# LoRa_Node_Module_V1_0.net
KiCad netlist of a schematic drawn in EAGLE
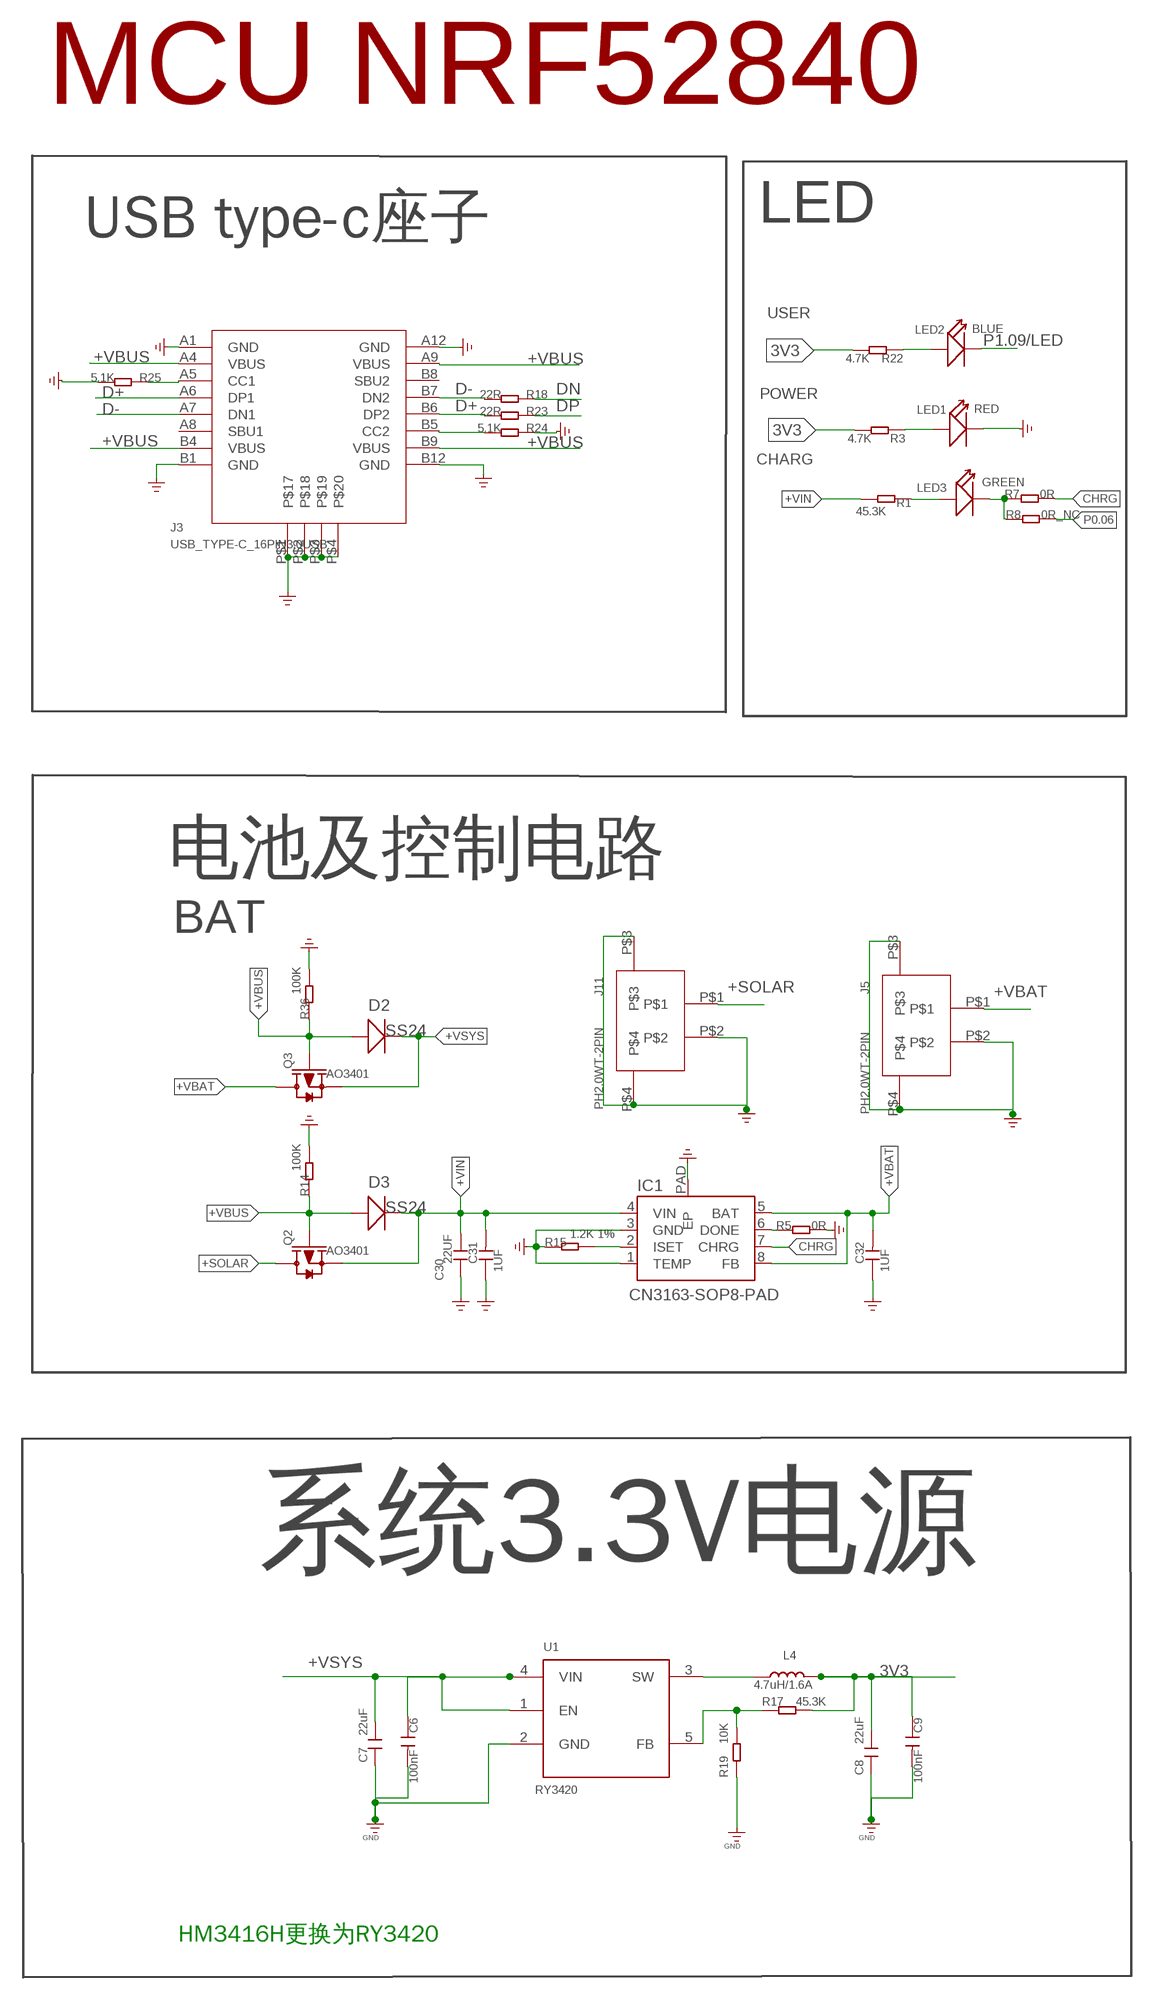
[diagram p0: schematic, sheet 1, part 1 of 2]
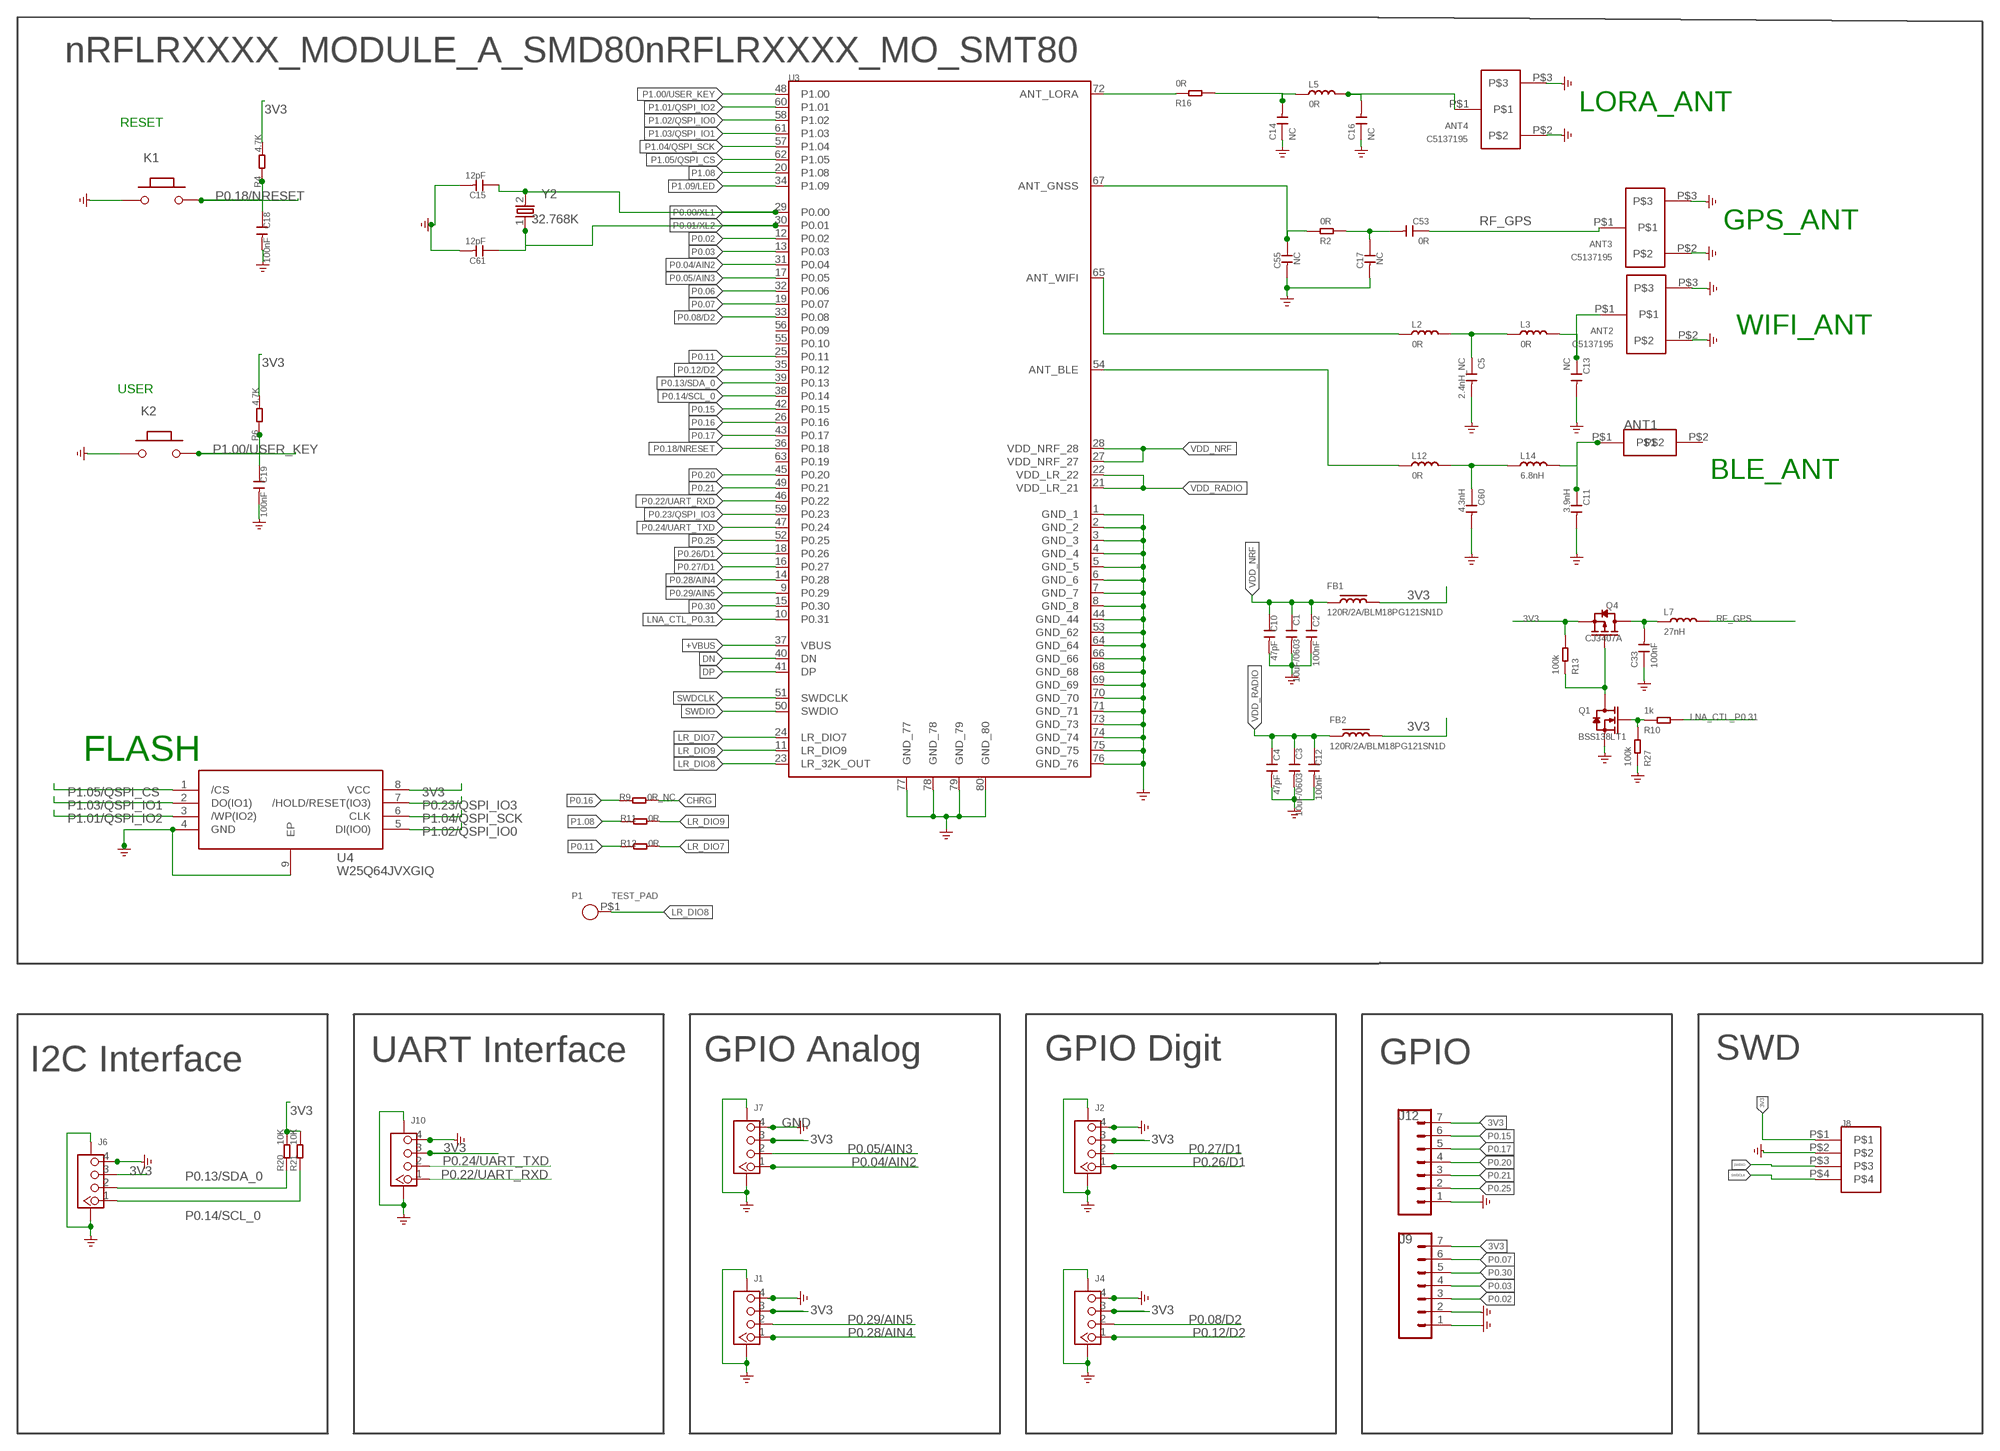
[diagram p1: schematic, sheet 1, part 2 of 2]

(export (version "E")
  (design (tool "Eeschema 10.0.6"))
  (components
    (comp (ref "ANT1")
      (value "ANT2.4G_BLE")
      (footprint "eagle-import:2.4G_BLE")
      (libsource (lib "eagle-import") (part "ANT2.4G_BLE"))
    )
    (comp (ref "ANT2")
      (value "C5137195")
      (footprint "eagle-import:MYSELF_IPEX1")
      (libsource (lib "eagle-import") (part "MYSELF_IPEX"))
    )
    (comp (ref "ANT3")
      (value "C5137195")
      (footprint "eagle-import:MYSELF_IPEX1")
      (libsource (lib "eagle-import") (part "MYSELF_IPEX"))
    )
    (comp (ref "ANT4")
      (value "C5137195")
      (footprint "eagle-import:MYSELF_IPEX1")
      (libsource (lib "eagle-import") (part "MYSELF_IPEX"))
    )
    (comp (ref "C1")
      (value "10uF/0603")
      (footprint "eagle-import:C0603")
      (libsource (lib "eagle-import") (part "C0603"))
    )
    (comp (ref "C2")
      (value "100nF")
      (footprint "eagle-import:C0402")
      (libsource (lib "eagle-import") (part "CAPC0402-1"))
    )
    (comp (ref "C3")
      (value "10uF/0603")
      (footprint "eagle-import:C0603")
      (libsource (lib "eagle-import") (part "C0603"))
    )
    (comp (ref "C4")
      (value "47pF")
      (footprint "eagle-import:C0402")
      (libsource (lib "eagle-import") (part "CAPC0402-1"))
    )
    (comp (ref "C5")
      (value "2.4nH_NC")
      (footprint "eagle-import:DISCRETE-NEW_C0402")
      (libsource (lib "eagle-import") (part "DISCRETE-NEW_CAP-0402"))
    )
    (comp (ref "C6")
      (value "100nF")
      (footprint "eagle-import:C0402")
      (libsource (lib "eagle-import") (part "CAPC0402-1"))
    )
    (comp (ref "C7")
      (value "22uF")
      (footprint "eagle-import:0603")
      (libsource (lib "eagle-import") (part "WGH_C0603"))
    )
    (comp (ref "C8")
      (value "22uF")
      (footprint "eagle-import:0603")
      (libsource (lib "eagle-import") (part "WGH_C0603"))
    )
    (comp (ref "C9")
      (value "100nF")
      (footprint "eagle-import:C0402")
      (libsource (lib "eagle-import") (part "CAPC0402-1"))
    )
    (comp (ref "C10")
      (value "47pF")
      (footprint "eagle-import:C0402")
      (libsource (lib "eagle-import") (part "CAPC0402-1"))
    )
    (comp (ref "C11")
      (value "3.9nH")
      (footprint "eagle-import:DISCRETE-NEW_C0402")
      (libsource (lib "eagle-import") (part "DISCRETE-NEW_CAP-0402"))
    )
    (comp (ref "C12")
      (value "100nF")
      (footprint "eagle-import:C0402")
      (libsource (lib "eagle-import") (part "CAPC0402-1"))
    )
    (comp (ref "C13")
      (value "NC")
      (footprint "eagle-import:DISCRETE-NEW_C0402")
      (libsource (lib "eagle-import") (part "DISCRETE-NEW_CAP-0402"))
    )
    (comp (ref "C14")
      (value "NC")
      (footprint "eagle-import:C0402")
      (libsource (lib "eagle-import") (part "CAP-0402"))
    )
    (comp (ref "C15")
      (value "12pF")
      (footprint "eagle-import:DISCRETE-NEW_C0402")
      (libsource (lib "eagle-import") (part "DISCRETE-NEW_CAP-0402"))
    )
    (comp (ref "C16")
      (value "NC")
      (footprint "eagle-import:C0402")
      (libsource (lib "eagle-import") (part "CAP-0402"))
    )
    (comp (ref "C17")
      (value "NC")
      (footprint "eagle-import:DISCRETE-NEW_C0402")
      (libsource (lib "eagle-import") (part "DISCRETE-NEW_CAP-0402"))
    )
    (comp (ref "C18")
      (value "100nF")
      (footprint "eagle-import:C0402")
      (libsource (lib "eagle-import") (part "CAPC0402-1"))
    )
    (comp (ref "C19")
      (value "100nF")
      (footprint "eagle-import:C0402")
      (libsource (lib "eagle-import") (part "CAPC0402-1"))
    )
    (comp (ref "C30")
      (value "22UF")
      (footprint "eagle-import:0603")
      (libsource (lib "eagle-import") (part "RC_C0603"))
    )
    (comp (ref "C31")
      (value "1UF")
      (footprint "eagle-import:C0603")
      (libsource (lib "eagle-import") (part "Lora_RA-08H_Node_ Board_C0603"))
    )
    (comp (ref "C32")
      (value "1UF")
      (footprint "eagle-import:C0603")
      (libsource (lib "eagle-import") (part "Lora_RA-08H_Node_ Board_C0603"))
    )
    (comp (ref "C33")
      (value "100nF")
      (footprint "eagle-import:C0402")
      (libsource (lib "eagle-import") (part "CAP-0402"))
    )
    (comp (ref "C53")
      (value "0R")
      (footprint "eagle-import:DISCRETE-NEW_C0402")
      (libsource (lib "eagle-import") (part "DISCRETE-NEW_CAP-0402"))
    )
    (comp (ref "C55")
      (value "NC")
      (footprint "eagle-import:DISCRETE-NEW_C0402")
      (libsource (lib "eagle-import") (part "DISCRETE-NEW_CAP-0402"))
    )
    (comp (ref "C60")
      (value "4.3nH")
      (footprint "eagle-import:DISCRETE-NEW_C0402")
      (libsource (lib "eagle-import") (part "DISCRETE-NEW_CAP-0402"))
    )
    (comp (ref "C61")
      (value "12pF")
      (footprint "eagle-import:DISCRETE-NEW_C0402")
      (libsource (lib "eagle-import") (part "DISCRETE-NEW_CAP-0402"))
    )
    (comp (ref "D2")
      (value "SS24")
      (footprint "eagle-import:SMA")
      (libsource (lib "eagle-import") (part "DIODEB130L-13-F"))
    )
    (comp (ref "D3")
      (value "SS24")
      (footprint "eagle-import:SMA")
      (libsource (lib "eagle-import") (part "DIODEB130L-13-F"))
    )
    (comp (ref "FB1")
      (value "120R/2A/BLM18PG121SN1D")
      (footprint "eagle-import:L0603")
      (libsource (lib "eagle-import") (part "FBL0603"))
    )
    (comp (ref "FB2")
      (value "120R/2A/BLM18PG121SN1D")
      (footprint "eagle-import:L0603")
      (libsource (lib "eagle-import") (part "FBL0603"))
    )
    (comp (ref "IC1")
      (value "CN3163-SOP8-PAD")
      (footprint "eagle-import:SOP8-PAD")
      (libsource (lib "eagle-import") (part "CN3163-SOP8-PAD"))
    )
    (comp (ref "J1")
      (value "CONNECTOR_TWIG-4P-2.0-SMD-FEMALE-REINFORCE90D")
      (footprint "eagle-import:CONNECTOR_4P-SMD-2.0-90D")
      (libsource (lib "eagle-import") (part "CONNECTOR_TWIG-4P-2.0-SMD-FEMALE-REINFORCE90D"))
    )
    (comp (ref "J2")
      (value "CONNECTOR_TWIG-4P-2.0-SMD-FEMALE-REINFORCE90D")
      (footprint "eagle-import:CONNECTOR_4P-SMD-2.0-90D")
      (libsource (lib "eagle-import") (part "CONNECTOR_TWIG-4P-2.0-SMD-FEMALE-REINFORCE90D"))
    )
    (comp (ref "J3")
      (value "USB_TYPE-C_16PIN3.0USB")
      (footprint "eagle-import:KEVIN_3.0TYPEC-SMD")
      (libsource (lib "eagle-import") (part "USB_TYPE-C_16PIN3.0USB"))
    )
    (comp (ref "J4")
      (value "CONNECTOR_TWIG-4P-2.0-SMD-FEMALE-REINFORCE90D")
      (footprint "eagle-import:CONNECTOR_4P-SMD-2.0-90D")
      (libsource (lib "eagle-import") (part "CONNECTOR_TWIG-4P-2.0-SMD-FEMALE-REINFORCE90D"))
    )
    (comp (ref "J5")
      (value "PH2.0WT-2PIN")
      (footprint "eagle-import:PH2.0WT-2PIN")
      (libsource (lib "eagle-import") (part "PH2.0WT-2PIN"))
    )
    (comp (ref "J6")
      (value "CONNECTOR_TWIG-4P-2.0-SMD-FEMALE-REINFORCE90D")
      (footprint "eagle-import:CONNECTOR_4P-SMD-2.0-90D")
      (libsource (lib "eagle-import") (part "CONNECTOR_TWIG-4P-2.0-SMD-FEMALE-REINFORCE90D"))
    )
    (comp (ref "J7")
      (value "CONNECTOR_TWIG-4P-2.0-SMD-FEMALE-REINFORCE90D")
      (footprint "eagle-import:CONNECTOR_4P-SMD-2.0-90D")
      (libsource (lib "eagle-import") (part "CONNECTOR_TWIG-4P-2.0-SMD-FEMALE-REINFORCE90D"))
    )
    (comp (ref "J8")
      (value "2.0MM-4P")
      (footprint "eagle-import:2.0MM-4P")
      (libsource (lib "eagle-import") (part "2.0MM-4P"))
    )
    (comp (ref "J9")
      (value "CONN_07NO_SILK")
      (footprint "eagle-import:1X07_NO_SILK")
      (libsource (lib "eagle-import") (part "CONN_07NO_SILK"))
    )
    (comp (ref "J10")
      (value "CONNECTOR_TWIG-4P-2.0-SMD-FEMALE-REINFORCE90D")
      (footprint "eagle-import:CONNECTOR_4P-SMD-2.0-90D")
      (libsource (lib "eagle-import") (part "CONNECTOR_TWIG-4P-2.0-SMD-FEMALE-REINFORCE90D"))
    )
    (comp (ref "J11")
      (value "PH2.0WT-2PIN")
      (footprint "eagle-import:PH2.0WT-2PIN")
      (libsource (lib "eagle-import") (part "PH2.0WT-2PIN"))
    )
    (comp (ref "J12")
      (value "CONN_07NO_SILK")
      (footprint "eagle-import:1X07_NO_SILK")
      (libsource (lib "eagle-import") (part "CONN_07NO_SILK"))
    )
    (comp (ref "K1")
      (value "BUTTON")
      (footprint "eagle-import:157SW")
      (libsource (lib "eagle-import") (part "PB157"))
    )
    (comp (ref "K2")
      (value "BUTTON")
      (footprint "eagle-import:157SW")
      (libsource (lib "eagle-import") (part "PB157"))
    )
    (comp (ref "L2")
      (value "0R")
      (footprint "eagle-import:XADOW-GPS-V2_DISCRETE-NEW_L0402")
      (libsource (lib "eagle-import") (part "XADOW-GPS-V2_DISCRETE-NEW_INDUCTOR/FERRITE-BEAD0402"))
    )
    (comp (ref "L3")
      (value "0R")
      (footprint "eagle-import:XADOW-GPS-V2_DISCRETE-NEW_L0402")
      (libsource (lib "eagle-import") (part "XADOW-GPS-V2_DISCRETE-NEW_INDUCTOR/FERRITE-BEAD0402"))
    )
    (comp (ref "L4")
      (value "4.7uH/1.6A")
      (footprint "eagle-import:A9G_DISCRETE_L0805")
      (libsource (lib "eagle-import") (part "A9G_DISCRETE_L0805"))
    )
    (comp (ref "L5")
      (value "0R")
      (footprint "eagle-import:L0402")
      (libsource (lib "eagle-import") (part "INDUCTOR'0402'"))
    )
    (comp (ref "L7")
      (value "27nH")
      (footprint "eagle-import:L0402")
      (libsource (lib "eagle-import") (part "INDUCTOR'0402'"))
    )
    (comp (ref "L12")
      (value "0R")
      (footprint "eagle-import:XADOW-GPS-V2_DISCRETE-NEW_L0402")
      (libsource (lib "eagle-import") (part "XADOW-GPS-V2_DISCRETE-NEW_INDUCTOR/FERRITE-BEAD0402"))
    )
    (comp (ref "L14")
      (value "6.8nH")
      (footprint "eagle-import:XADOW-GPS-V2_DISCRETE-NEW_L0402")
      (libsource (lib "eagle-import") (part "XADOW-GPS-V2_DISCRETE-NEW_INDUCTOR/FERRITE-BEAD0402"))
    )
    (comp (ref "LED1")
      (value "RED")
      (footprint "eagle-import:DISCRETE_LED-0603")
      (libsource (lib "eagle-import") (part "DISCRETE_LED0603"))
    )
    (comp (ref "LED2")
      (value "BLUE")
      (footprint "eagle-import:DISCRETE_LED-0603")
      (libsource (lib "eagle-import") (part "DISCRETE_LED0603"))
    )
    (comp (ref "LED3")
      (value "GREEN")
      (footprint "eagle-import:LED0603")
      (libsource (lib "eagle-import") (part "LED-SMT0603"))
    )
    (comp (ref "P1")
      (value "TEST_PAD")
      (footprint "eagle-import:TEST_PAD-1.5MM")
      (libsource (lib "eagle-import") (part "TEST_PADPAD-1.5MM"))
    )
    (comp (ref "Q1")
      (value "BSS138LT1")
      (footprint "eagle-import:SOT-323")
      (libsource (lib "eagle-import") (part "MOSFET-N-SI1304BDL"))
    )
    (comp (ref "Q2")
      (value "AO3401")
      (footprint "eagle-import:PMOS_SOT23")
      (libsource (lib "eagle-import") (part "MOSFET-PSOT23"))
    )
    (comp (ref "Q3")
      (value "AO3401")
      (footprint "eagle-import:PMOS_SOT23")
      (libsource (lib "eagle-import") (part "MOSFET-PSOT23"))
    )
    (comp (ref "Q4")
      (value "CJ3407A")
      (footprint "eagle-import:SOT-323")
      (libsource (lib "eagle-import") (part "MOSFET-P-SOT323"))
    )
    (comp (ref "R1")
      (value "45.3K")
      (footprint "eagle-import:R0402")
      (libsource (lib "eagle-import") (part "Lora_RA-08H_Node_ Board_RES-0402"))
    )
    (comp (ref "R2")
      (value "0R")
      (footprint "eagle-import:DISCRETE-NEW_R0402")
      (libsource (lib "eagle-import") (part "DISCRETE-NEW_RES-0402"))
    )
    (comp (ref "R3")
      (value "4.7K")
      (footprint "eagle-import:0402")
      (libsource (lib "eagle-import") (part "R0402-1"))
    )
    (comp (ref "R4")
      (value "4.7K")
      (footprint "eagle-import:R0402")
      (libsource (lib "eagle-import") (part "R0402-0402"))
    )
    (comp (ref "R5")
      (value "0R")
      (footprint "eagle-import:R0402")
      (libsource (lib "eagle-import") (part "LoraWAN_Gateway_Mainboard_RES-0402"))
    )
    (comp (ref "R6")
      (value "4.7K")
      (footprint "eagle-import:R0402")
      (libsource (lib "eagle-import") (part "R0402-0402"))
    )
    (comp (ref "R7")
      (value "0R")
      (footprint "eagle-import:R0402")
      (libsource (lib "eagle-import") (part "LoraWAN_Gateway_Mainboard_RES-0402"))
    )
    (comp (ref "R8")
      (value "0R_NC")
      (footprint "eagle-import:R0402")
      (libsource (lib "eagle-import") (part "LoraWAN_Gateway_Mainboard_RES-0402"))
    )
    (comp (ref "R9")
      (value "0R_NC")
      (footprint "eagle-import:R0402")
      (libsource (lib "eagle-import") (part "LoraWAN_Gateway_Mainboard_RES-0402"))
    )
    (comp (ref "R10")
      (value "1k")
      (footprint "eagle-import:R0402")
      (libsource (lib "eagle-import") (part "RES-0402"))
    )
    (comp (ref "R11")
      (value "0R")
      (footprint "eagle-import:R0402")
      (libsource (lib "eagle-import") (part "LoraWAN_Gateway_Mainboard_RES-0402"))
    )
    (comp (ref "R12")
      (value "0R")
      (footprint "eagle-import:R0402")
      (libsource (lib "eagle-import") (part "LoraWAN_Gateway_Mainboard_RES-0402"))
    )
    (comp (ref "R13")
      (value "100k")
      (footprint "eagle-import:R0402")
      (libsource (lib "eagle-import") (part "RES-0402"))
    )
    (comp (ref "R14")
      (value "100K")
      (footprint "eagle-import:R0402")
      (libsource (lib "eagle-import") (part "Lora_RA-08H_Node_ Board_RES-0402"))
    )
    (comp (ref "R15")
      (value "1.2K 1%")
      (footprint "eagle-import:R0402")
      (libsource (lib "eagle-import") (part "Lora_RA-08H_Node_ Board_RES-0402"))
    )
    (comp (ref "R16")
      (value "0R")
      (footprint "eagle-import:DISCRETE-NEW_R0402")
      (libsource (lib "eagle-import") (part "DISCRETE-NEW_RES-0402"))
    )
    (comp (ref "R17")
      (value "45.3K")
      (footprint "eagle-import:0402")
      (libsource (lib "eagle-import") (part "R0402-1"))
    )
    (comp (ref "R18")
      (value "22R")
      (footprint "eagle-import:0402")
      (libsource (lib "eagle-import") (part "R0402-1"))
    )
    (comp (ref "R19")
      (value "10K")
      (footprint "eagle-import:0402")
      (libsource (lib "eagle-import") (part "R0402-1"))
    )
    (comp (ref "R20")
      (value "10K")
      (footprint "eagle-import:0402")
      (libsource (lib "eagle-import") (part "R0402-1"))
    )
    (comp (ref "R21")
      (value "10K")
      (footprint "eagle-import:0402")
      (libsource (lib "eagle-import") (part "R0402-1"))
    )
    (comp (ref "R22")
      (value "4.7K")
      (footprint "eagle-import:0402")
      (libsource (lib "eagle-import") (part "R0402-1"))
    )
    (comp (ref "R23")
      (value "22R")
      (footprint "eagle-import:0402")
      (libsource (lib "eagle-import") (part "R0402-1"))
    )
    (comp (ref "R24")
      (value "5.1K")
      (footprint "eagle-import:0402")
      (libsource (lib "eagle-import") (part "R0402-1"))
    )
    (comp (ref "R25")
      (value "5.1K")
      (footprint "eagle-import:0402")
      (libsource (lib "eagle-import") (part "R0402-1"))
    )
    (comp (ref "R27")
      (value "100k")
      (footprint "eagle-import:R0402")
      (libsource (lib "eagle-import") (part "RES-0402"))
    )
    (comp (ref "R36")
      (value "100K")
      (footprint "eagle-import:R0402")
      (libsource (lib "eagle-import") (part "Lora_RA-08H_Node_ Board_RES-0402"))
    )
    (comp (ref "U1")
      (value "RY3420")
      (footprint "eagle-import:CROWBOT_-V1.0-20220525_A_XBJ_SOT23-5")
      (libsource (lib "eagle-import") (part "CROWBOT_-V1.0-20220525_A_XBJ_HM3420B"))
    )
    (comp (ref "U3")
      (value "nRFLRXXXX_MODULE_A_SMD80nRFLRXXXX_MO_SMT80")
      (footprint "eagle-import:LR11XX_MO_A_SMD80")
      (libsource (lib "eagle-import") (part "LR11XX_MODULE_A_SMD80LR11XX_MO_SMT80"))
    )
    (comp (ref "U4")
      (value "W25Q64JVXGIQ")
      (footprint "eagle-import:XSON-EP(4×4)")
      (libsource (lib "eagle-import") (part "W25Q64JVXGIQ"))
    )
    (comp (ref "Y2")
      (value "32.768K")
      (footprint "eagle-import:NORDIC_NRF_XTAL_3215_N")
      (libsource (lib "eagle-import") (part "NORDIC_NRF_XTAL_32KHZ"))
    )
  )
  (nets
    (net (code "1") (name "+SOLAR") (class "Default")
      (node (ref "J11") (pin "P$1") (pinfunction "P$1_P$1") (pintype "bidirectional"))
      (node (ref "Q2") (pin "3") (pinfunction "D_3") (pintype "passive"))
    )
    (net (code "2") (name "+VBAT") (class "Default")
      (node (ref "C32") (pin "2") (pinfunction "2_2") (pintype "passive"))
      (node (ref "IC1") (pin "5") (pinfunction "BAT_5") (pintype "bidirectional"))
      (node (ref "IC1") (pin "8") (pinfunction "FB_8") (pintype "bidirectional"))
      (node (ref "J5") (pin "P$1") (pinfunction "P$1_P$1") (pintype "bidirectional"))
      (node (ref "Q3") (pin "3") (pinfunction "D_3") (pintype "passive"))
    )
    (net (code "3") (name "+VBUS") (class "Default")
      (node (ref "D2") (pin "2") (pinfunction "+_2") (pintype "passive"))
      (node (ref "D3") (pin "2") (pinfunction "+_2") (pintype "passive"))
      (node (ref "J3") (pin "A4") (pinfunction "VBUS_A4") (pintype "bidirectional"))
      (node (ref "J3") (pin "A9") (pinfunction "VBUS_A9") (pintype "bidirectional"))
      (node (ref "J3") (pin "B4") (pinfunction "VBUS_B4") (pintype "bidirectional"))
      (node (ref "J3") (pin "B9") (pinfunction "VBUS_B9") (pintype "bidirectional"))
      (node (ref "Q2") (pin "1") (pinfunction "G_1") (pintype "passive"))
      (node (ref "Q3") (pin "1") (pinfunction "G_1") (pintype "passive"))
      (node (ref "R14") (pin "1") (pinfunction "1_1") (pintype "passive"))
      (node (ref "R36") (pin "1") (pinfunction "1_1") (pintype "passive"))
      (node (ref "U3") (pin "37") (pinfunction "VBUS_37") (pintype "bidirectional"))
    )
    (net (code "4") (name "+VIN") (class "Default")
      (node (ref "C30") (pin "2") (pinfunction "2_2") (pintype "passive"))
      (node (ref "C31") (pin "2") (pinfunction "2_2") (pintype "passive"))
      (node (ref "D3") (pin "1") (pinfunction "-_1") (pintype "passive"))
      (node (ref "IC1") (pin "4") (pinfunction "VIN_4") (pintype "bidirectional"))
      (node (ref "Q2") (pin "2") (pinfunction "S_2") (pintype "passive"))
      (node (ref "R1") (pin "2") (pinfunction "2_2") (pintype "passive"))
    )
    (net (code "5") (name "+VSYS") (class "Default")
      (node (ref "C6") (pin "1") (pinfunction "1_1") (pintype "passive"))
      (node (ref "C7") (pin "2") (pinfunction "2_2") (pintype "passive"))
      (node (ref "D2") (pin "1") (pinfunction "-_1") (pintype "passive"))
      (node (ref "Q3") (pin "2") (pinfunction "S_2") (pintype "passive"))
      (node (ref "U1") (pin "1") (pinfunction "EN_1") (pintype "bidirectional"))
      (node (ref "U1") (pin "4") (pinfunction "VIN_4") (pintype "bidirectional"))
    )
    (net (code "6") (name "/D+") (class "Default")
      (node (ref "J3") (pin "A6") (pinfunction "DP1_A6") (pintype "bidirectional"))
      (node (ref "J3") (pin "B6") (pinfunction "DP2_B6") (pintype "bidirectional"))
      (node (ref "R23") (pin "2") (pinfunction "2_2") (pintype "passive"))
    )
    (net (code "7") (name "/D-") (class "Default")
      (node (ref "J3") (pin "A7") (pinfunction "DN1_A7") (pintype "bidirectional"))
      (node (ref "J3") (pin "B7") (pinfunction "DN2_B7") (pintype "bidirectional"))
      (node (ref "R18") (pin "2") (pinfunction "2_2") (pintype "passive"))
    )
    (net (code "8") (name "/RF_GPS") (class "Default")
      (node (ref "ANT3") (pin "P$1") (pinfunction "P$1_P$1") (pintype "bidirectional"))
      (node (ref "C53") (pin "1") (pinfunction "1_1") (pintype "passive"))
      (node (ref "L7") (pin "2") (pinfunction "2_2") (pintype "passive"))
    )
    (net (code "9") (name "3V3") (class "Default")
      (node (ref "C8") (pin "2") (pinfunction "2_2") (pintype "passive"))
      (node (ref "C9") (pin "1") (pinfunction "1_1") (pintype "passive"))
      (node (ref "FB1") (pin "2") (pinfunction "2_2") (pintype "passive"))
      (node (ref "FB2") (pin "2") (pinfunction "2_2") (pintype "passive"))
      (node (ref "J1") (pin "3") (pinfunction "3_3") (pintype "bidirectional"))
      (node (ref "J10") (pin "3") (pinfunction "3_3") (pintype "bidirectional"))
      (node (ref "J12") (pin "7") (pinfunction "7_7") (pintype "passive"))
      (node (ref "J2") (pin "3") (pinfunction "3_3") (pintype "bidirectional"))
      (node (ref "J4") (pin "3") (pinfunction "3_3") (pintype "bidirectional"))
      (node (ref "J6") (pin "3") (pinfunction "3_3") (pintype "bidirectional"))
      (node (ref "J7") (pin "3") (pinfunction "3_3") (pintype "bidirectional"))
      (node (ref "J8") (pin "P$1") (pinfunction "P$1_P$1") (pintype "bidirectional"))
      (node (ref "J9") (pin "7") (pinfunction "7_7") (pintype "passive"))
      (node (ref "L4") (pin "2") (pinfunction "2_2") (pintype "passive"))
      (node (ref "Q4") (pin "2") (pinfunction "S_2") (pintype "passive"))
      (node (ref "R13") (pin "2") (pinfunction "2_2") (pintype "passive"))
      (node (ref "R17") (pin "2") (pinfunction "2_2") (pintype "passive"))
      (node (ref "R20") (pin "2") (pinfunction "2_2") (pintype "passive"))
      (node (ref "R21") (pin "2") (pinfunction "2_2") (pintype "passive"))
      (node (ref "R22") (pin "2") (pinfunction "2_2") (pintype "passive"))
      (node (ref "R3") (pin "2") (pinfunction "2_2") (pintype "passive"))
      (node (ref "R4") (pin "2") (pinfunction "2_2") (pintype "passive"))
      (node (ref "R6") (pin "2") (pinfunction "2_2") (pintype "passive"))
      (node (ref "U4") (pin "8") (pinfunction "VCC_8") (pintype "bidirectional"))
    )
    (net (code "10") (name "A_XBJ_POWER_OR_GND__GND_POWER") (class "Default")
      (node (ref "ANT2") (pin "P$2") (pinfunction "P$2_P$2") (pintype "bidirectional"))
      (node (ref "ANT2") (pin "P$3") (pinfunction "P$3_P$3") (pintype "bidirectional"))
      (node (ref "ANT3") (pin "P$2") (pinfunction "P$2_P$2") (pintype "bidirectional"))
      (node (ref "ANT3") (pin "P$3") (pinfunction "P$3_P$3") (pintype "bidirectional"))
      (node (ref "ANT4") (pin "P$2") (pinfunction "P$2_P$2") (pintype "bidirectional"))
      (node (ref "ANT4") (pin "P$3") (pinfunction "P$3_P$3") (pintype "bidirectional"))
      (node (ref "C1") (pin "2") (pinfunction "2_2") (pintype "passive"))
      (node (ref "C10") (pin "2") (pinfunction "2_2") (pintype "passive"))
      (node (ref "C11") (pin "2") (pinfunction "2_2") (pintype "passive"))
      (node (ref "C12") (pin "2") (pinfunction "2_2") (pintype "passive"))
      (node (ref "C13") (pin "2") (pinfunction "2_2") (pintype "passive"))
      (node (ref "C14") (pin "1") (pinfunction "1_1") (pintype "passive"))
      (node (ref "C15") (pin "2") (pinfunction "2_2") (pintype "passive"))
      (node (ref "C16") (pin "1") (pinfunction "1_1") (pintype "passive"))
      (node (ref "C17") (pin "2") (pinfunction "2_2") (pintype "passive"))
      (node (ref "C18") (pin "2") (pinfunction "2_2") (pintype "passive"))
      (node (ref "C19") (pin "2") (pinfunction "2_2") (pintype "passive"))
      (node (ref "C2") (pin "2") (pinfunction "2_2") (pintype "passive"))
      (node (ref "C3") (pin "2") (pinfunction "2_2") (pintype "passive"))
      (node (ref "C30") (pin "1") (pinfunction "1_1") (pintype "passive"))
      (node (ref "C31") (pin "1") (pinfunction "1_1") (pintype "passive"))
      (node (ref "C32") (pin "1") (pinfunction "1_1") (pintype "passive"))
      (node (ref "C33") (pin "1") (pinfunction "1_1") (pintype "passive"))
      (node (ref "C4") (pin "2") (pinfunction "2_2") (pintype "passive"))
      (node (ref "C5") (pin "2") (pinfunction "2_2") (pintype "passive"))
      (node (ref "C55") (pin "2") (pinfunction "2_2") (pintype "passive"))
      (node (ref "C6") (pin "2") (pinfunction "2_2") (pintype "passive"))
      (node (ref "C60") (pin "2") (pinfunction "2_2") (pintype "passive"))
      (node (ref "C61") (pin "2") (pinfunction "2_2") (pintype "passive"))
      (node (ref "C7") (pin "1") (pinfunction "1_1") (pintype "passive"))
      (node (ref "C8") (pin "1") (pinfunction "1_1") (pintype "passive"))
      (node (ref "C9") (pin "2") (pinfunction "2_2") (pintype "passive"))
      (node (ref "IC1") (pin "1") (pinfunction "TEMP_1") (pintype "bidirectional"))
      (node (ref "IC1") (pin "3") (pinfunction "GND_3") (pintype "bidirectional"))
      (node (ref "IC1") (pin "PAD") (pinfunction "EP_PAD") (pintype "bidirectional"))
      (node (ref "J1") (pin "4") (pinfunction "4_4") (pintype "bidirectional"))
      (node (ref "J1") (pin "SS1") (pinfunction "SS1_SS1") (pintype "bidirectional"))
      (node (ref "J1") (pin "SS2") (pinfunction "SS2_SS2") (pintype "bidirectional"))
      (node (ref "J10") (pin "4") (pinfunction "4_4") (pintype "bidirectional"))
      (node (ref "J10") (pin "SS1") (pinfunction "SS1_SS1") (pintype "bidirectional"))
      (node (ref "J10") (pin "SS2") (pinfunction "SS2_SS2") (pintype "bidirectional"))
      (node (ref "J11") (pin "P$2") (pinfunction "P$2_P$2") (pintype "bidirectional"))
      (node (ref "J11") (pin "P$3") (pinfunction "P$3_P$3") (pintype "bidirectional"))
      (node (ref "J11") (pin "P$4") (pinfunction "P$4_P$4") (pintype "bidirectional"))
      (node (ref "J12") (pin "1") (pinfunction "1_1") (pintype "passive"))
      (node (ref "J2") (pin "4") (pinfunction "4_4") (pintype "bidirectional"))
      (node (ref "J2") (pin "SS1") (pinfunction "SS1_SS1") (pintype "bidirectional"))
      (node (ref "J2") (pin "SS2") (pinfunction "SS2_SS2") (pintype "bidirectional"))
      (node (ref "J3") (pin "A1") (pinfunction "GND_A1") (pintype "bidirectional"))
      (node (ref "J3") (pin "A12") (pinfunction "GND_A12") (pintype "bidirectional"))
      (node (ref "J3") (pin "B1") (pinfunction "GND_B1") (pintype "bidirectional"))
      (node (ref "J3") (pin "B12") (pinfunction "GND_B12") (pintype "bidirectional"))
      (node (ref "J3") (pin "P$1") (pinfunction "P$17_P$1") (pintype "bidirectional"))
      (node (ref "J3") (pin "P$2") (pinfunction "P$18_P$2") (pintype "bidirectional"))
      (node (ref "J3") (pin "P$3") (pinfunction "P$19_P$3") (pintype "bidirectional"))
      (node (ref "J3") (pin "P$4") (pinfunction "P$20_P$4") (pintype "bidirectional"))
      (node (ref "J4") (pin "4") (pinfunction "4_4") (pintype "bidirectional"))
      (node (ref "J4") (pin "SS1") (pinfunction "SS1_SS1") (pintype "bidirectional"))
      (node (ref "J4") (pin "SS2") (pinfunction "SS2_SS2") (pintype "bidirectional"))
      (node (ref "J5") (pin "P$2") (pinfunction "P$2_P$2") (pintype "bidirectional"))
      (node (ref "J5") (pin "P$3") (pinfunction "P$3_P$3") (pintype "bidirectional"))
      (node (ref "J5") (pin "P$4") (pinfunction "P$4_P$4") (pintype "bidirectional"))
      (node (ref "J6") (pin "4") (pinfunction "4_4") (pintype "bidirectional"))
      (node (ref "J6") (pin "SS1") (pinfunction "SS1_SS1") (pintype "bidirectional"))
      (node (ref "J6") (pin "SS2") (pinfunction "SS2_SS2") (pintype "bidirectional"))
      (node (ref "J7") (pin "4") (pinfunction "4_4") (pintype "bidirectional"))
      (node (ref "J7") (pin "SS1") (pinfunction "SS1_SS1") (pintype "bidirectional"))
      (node (ref "J7") (pin "SS2") (pinfunction "SS2_SS2") (pintype "bidirectional"))
      (node (ref "J8") (pin "P$2") (pinfunction "P$2_P$2") (pintype "bidirectional"))
      (node (ref "J9") (pin "1") (pinfunction "1_1") (pintype "passive"))
      (node (ref "J9") (pin "2") (pinfunction "2_2") (pintype "passive"))
      (node (ref "K1") (pin "1") (pinfunction "1_1") (pintype "passive"))
      (node (ref "K2") (pin "1") (pinfunction "1_1") (pintype "passive"))
      (node (ref "LED1") (pin "-") (pinfunction "-_-") (pintype "passive"))
      (node (ref "Q1") (pin "2") (pinfunction "S_2") (pintype "passive"))
      (node (ref "R14") (pin "2") (pinfunction "2_2") (pintype "passive"))
      (node (ref "R15") (pin "1") (pinfunction "1_1") (pintype "passive"))
      (node (ref "R19") (pin "1") (pinfunction "1_1") (pintype "passive"))
      (node (ref "R24") (pin "1") (pinfunction "1_1") (pintype "passive"))
      (node (ref "R25") (pin "2") (pinfunction "2_2") (pintype "passive"))
      (node (ref "R27") (pin "1") (pinfunction "1_1") (pintype "passive"))
      (node (ref "R36") (pin "2") (pinfunction "2_2") (pintype "passive"))
      (node (ref "R5") (pin "2") (pinfunction "2_2") (pintype "passive"))
      (node (ref "U1") (pin "2") (pinfunction "GND_2") (pintype "bidirectional"))
      (node (ref "U3") (pin "1") (pinfunction "GND_1_1") (pintype "bidirectional"))
      (node (ref "U3") (pin "2") (pinfunction "GND_2_2") (pintype "bidirectional"))
      (node (ref "U3") (pin "3") (pinfunction "GND_3_3") (pintype "bidirectional"))
      (node (ref "U3") (pin "4") (pinfunction "GND_4_4") (pintype "bidirectional"))
      (node (ref "U3") (pin "44") (pinfunction "GND_44_44") (pintype "bidirectional"))
      (node (ref "U3") (pin "5") (pinfunction "GND_5_5") (pintype "bidirectional"))
      (node (ref "U3") (pin "53") (pinfunction "GND_62_53") (pintype "bidirectional"))
      (node (ref "U3") (pin "6") (pinfunction "GND_6_6") (pintype "bidirectional"))
      (node (ref "U3") (pin "64") (pinfunction "GND_64_64") (pintype "bidirectional"))
      (node (ref "U3") (pin "66") (pinfunction "GND_66_66") (pintype "bidirectional"))
      (node (ref "U3") (pin "68") (pinfunction "GND_68_68") (pintype "bidirectional"))
      (node (ref "U3") (pin "69") (pinfunction "GND_69_69") (pintype "bidirectional"))
      (node (ref "U3") (pin "7") (pinfunction "GND_7_7") (pintype "bidirectional"))
      (node (ref "U3") (pin "70") (pinfunction "GND_70_70") (pintype "bidirectional"))
      (node (ref "U3") (pin "71") (pinfunction "GND_71_71") (pintype "bidirectional"))
      (node (ref "U3") (pin "73") (pinfunction "GND_73_73") (pintype "bidirectional"))
      (node (ref "U3") (pin "74") (pinfunction "GND_74_74") (pintype "bidirectional"))
      (node (ref "U3") (pin "75") (pinfunction "GND_75_75") (pintype "bidirectional"))
      (node (ref "U3") (pin "76") (pinfunction "GND_76_76") (pintype "bidirectional"))
      (node (ref "U3") (pin "77") (pinfunction "GND_77_77") (pintype "bidirectional"))
      (node (ref "U3") (pin "78") (pinfunction "GND_78_78") (pintype "bidirectional"))
      (node (ref "U3") (pin "79") (pinfunction "GND_79_79") (pintype "bidirectional"))
      (node (ref "U3") (pin "8") (pinfunction "GND_8_8") (pintype "bidirectional"))
      (node (ref "U3") (pin "80") (pinfunction "GND_80_80") (pintype "bidirectional"))
      (node (ref "U4") (pin "4") (pinfunction "GND_4") (pintype "bidirectional"))
      (node (ref "U4") (pin "9") (pinfunction "EP_9") (pintype "bidirectional"))
    )
    (net (code "11") (name "CHRG") (class "Default")
      (node (ref "IC1") (pin "7") (pinfunction "CHRG_7") (pintype "bidirectional"))
      (node (ref "R7") (pin "2") (pinfunction "2_2") (pintype "passive"))
      (node (ref "R9") (pin "2") (pinfunction "2_2") (pintype "passive"))
    )
    (net (code "12") (name "DN") (class "Default")
      (node (ref "R18") (pin "1") (pinfunction "1_1") (pintype "passive"))
      (node (ref "U3") (pin "40") (pinfunction "DN_40") (pintype "bidirectional"))
    )
    (net (code "13") (name "DP") (class "Default")
      (node (ref "R23") (pin "1") (pinfunction "1_1") (pintype "passive"))
      (node (ref "U3") (pin "41") (pinfunction "DP_41") (pintype "bidirectional"))
    )
    (net (code "14") (name "LNA_CTL_P0.31") (class "Default")
      (node (ref "R10") (pin "2") (pinfunction "2_2") (pintype "passive"))
      (node (ref "U3") (pin "10") (pinfunction "P0.31_10") (pintype "bidirectional"))
    )
    (net (code "15") (name "LR_DIO7") (class "Default")
      (node (ref "R12") (pin "2") (pinfunction "2_2") (pintype "passive"))
      (node (ref "U3") (pin "24") (pinfunction "LR_DIO7_24") (pintype "bidirectional"))
    )
    (net (code "16") (name "LR_DIO8") (class "Default")
      (node (ref "P1") (pin "P$1") (pinfunction "P$1_P$1") (pintype "bidirectional"))
      (node (ref "U3") (pin "23") (pinfunction "LR_32K_OUT_23") (pintype "bidirectional"))
    )
    (net (code "17") (name "LR_DIO9") (class "Default")
      (node (ref "R11") (pin "2") (pinfunction "2_2") (pintype "passive"))
      (node (ref "U3") (pin "11") (pinfunction "LR_DIO9_11") (pintype "bidirectional"))
    )
    (net (code "18") (name "Net-(ANT1-PadP$1)") (class "Default")
      (node (ref "ANT1") (pin "P$1") (pinfunction "P$1_P$1") (pintype "bidirectional"))
      (node (ref "C11") (pin "1") (pinfunction "1_1") (pintype "passive"))
      (node (ref "L14") (pin "2") (pinfunction "2_2") (pintype "passive"))
    )
    (net (code "19") (name "Net-(ANT2-PadP$1)") (class "Default")
      (node (ref "ANT2") (pin "P$1") (pinfunction "P$1_P$1") (pintype "bidirectional"))
      (node (ref "C13") (pin "1") (pinfunction "1_1") (pintype "passive"))
      (node (ref "L3") (pin "2") (pinfunction "2_2") (pintype "passive"))
    )
    (net (code "20") (name "Net-(ANT4-PadP$1)") (class "Default")
      (node (ref "ANT4") (pin "P$1") (pinfunction "P$1_P$1") (pintype "bidirectional"))
      (node (ref "C16") (pin "2") (pinfunction "2_2") (pintype "passive"))
      (node (ref "L5") (pin "2") (pinfunction "2_2") (pintype "passive"))
    )
    (net (code "21") (name "Net-(C5-Pad1)") (class "Default")
      (node (ref "C5") (pin "1") (pinfunction "1_1") (pintype "passive"))
      (node (ref "L2") (pin "2") (pinfunction "2_2") (pintype "passive"))
      (node (ref "L3") (pin "1") (pinfunction "1_1") (pintype "passive"))
    )
    (net (code "22") (name "Net-(C14-Pad2)") (class "Default")
      (node (ref "C14") (pin "2") (pinfunction "2_2") (pintype "passive"))
      (node (ref "L5") (pin "1") (pinfunction "1_1") (pintype "passive"))
      (node (ref "R16") (pin "2") (pinfunction "2_2") (pintype "passive"))
    )
    (net (code "23") (name "Net-(C17-Pad1)") (class "Default")
      (node (ref "C17") (pin "1") (pinfunction "1_1") (pintype "passive"))
      (node (ref "C53") (pin "2") (pinfunction "2_2") (pintype "passive"))
      (node (ref "R2") (pin "2") (pinfunction "2_2") (pintype "passive"))
    )
    (net (code "24") (name "Net-(C60-Pad1)") (class "Default")
      (node (ref "C60") (pin "1") (pinfunction "1_1") (pintype "passive"))
      (node (ref "L12") (pin "2") (pinfunction "2_2") (pintype "passive"))
      (node (ref "L14") (pin "1") (pinfunction "1_1") (pintype "passive"))
    )
    (net (code "25") (name "Net-(IC1-DONE)") (class "Default")
      (node (ref "IC1") (pin "6") (pinfunction "DONE_6") (pintype "bidirectional"))
      (node (ref "R5") (pin "1") (pinfunction "1_1") (pintype "passive"))
    )
    (net (code "26") (name "Net-(IC1-ISET)") (class "Default")
      (node (ref "IC1") (pin "2") (pinfunction "ISET_2") (pintype "bidirectional"))
      (node (ref "R15") (pin "2") (pinfunction "2_2") (pintype "passive"))
    )
    (net (code "27") (name "Net-(J3-CC1)") (class "Default")
      (node (ref "J3") (pin "A5") (pinfunction "CC1_A5") (pintype "bidirectional"))
      (node (ref "R25") (pin "1") (pinfunction "1_1") (pintype "passive"))
    )
    (net (code "28") (name "Net-(J3-CC2)") (class "Default")
      (node (ref "J3") (pin "B5") (pinfunction "CC2_B5") (pintype "bidirectional"))
      (node (ref "R24") (pin "2") (pinfunction "2_2") (pintype "passive"))
    )
    (net (code "29") (name "Net-(LED1-Pad+)") (class "Default")
      (node (ref "LED1") (pin "+") (pinfunction "+_+") (pintype "passive"))
      (node (ref "R3") (pin "1") (pinfunction "1_1") (pintype "passive"))
    )
    (net (code "30") (name "Net-(LED2-Pad+)") (class "Default")
      (node (ref "LED2") (pin "+") (pinfunction "+_+") (pintype "passive"))
      (node (ref "R22") (pin "1") (pinfunction "1_1") (pintype "passive"))
    )
    (net (code "31") (name "Net-(LED3-Pad+)") (class "Default")
      (node (ref "LED3") (pin "+") (pinfunction "+_+") (pintype "passive"))
      (node (ref "R1") (pin "1") (pinfunction "1_1") (pintype "passive"))
    )
    (net (code "32") (name "Net-(LED3-Pad-)") (class "Default")
      (node (ref "LED3") (pin "-") (pinfunction "-_-") (pintype "passive"))
      (node (ref "R7") (pin "1") (pinfunction "1_1") (pintype "passive"))
      (node (ref "R8") (pin "1") (pinfunction "1_1") (pintype "passive"))
    )
    (net (code "33") (name "Net-(Q1-D)") (class "Default")
      (node (ref "Q1") (pin "3") (pinfunction "D_3") (pintype "passive"))
      (node (ref "Q4") (pin "1") (pinfunction "G_1") (pintype "passive"))
      (node (ref "R13") (pin "1") (pinfunction "1_1") (pintype "passive"))
    )
    (net (code "34") (name "Net-(Q1-G)") (class "Default")
      (node (ref "Q1") (pin "1") (pinfunction "G_1") (pintype "passive"))
      (node (ref "R10") (pin "1") (pinfunction "1_1") (pintype "passive"))
      (node (ref "R27") (pin "2") (pinfunction "2_2") (pintype "passive"))
    )
    (net (code "35") (name "Net-(Q4-D)") (class "Default")
      (node (ref "C33") (pin "2") (pinfunction "2_2") (pintype "passive"))
      (node (ref "L7") (pin "1") (pinfunction "1_1") (pintype "passive"))
      (node (ref "Q4") (pin "3") (pinfunction "D_3") (pintype "passive"))
    )
    (net (code "36") (name "Net-(U1-FB)") (class "Default")
      (node (ref "R17") (pin "1") (pinfunction "1_1") (pintype "passive"))
      (node (ref "R19") (pin "2") (pinfunction "2_2") (pintype "passive"))
      (node (ref "U1") (pin "5") (pinfunction "FB_5") (pintype "bidirectional"))
    )
    (net (code "37") (name "Net-(U1-SW)") (class "Default")
      (node (ref "L4") (pin "1") (pinfunction "1_1") (pintype "passive"))
      (node (ref "U1") (pin "3") (pinfunction "SW_3") (pintype "bidirectional"))
    )
    (net (code "38") (name "Net-(U3-ANT_BLE)") (class "Default")
      (node (ref "L12") (pin "1") (pinfunction "1_1") (pintype "passive"))
      (node (ref "U3") (pin "54") (pinfunction "ANT_BLE_54") (pintype "bidirectional"))
    )
    (net (code "39") (name "Net-(U3-ANT_GNSS)") (class "Default")
      (node (ref "C55") (pin "1") (pinfunction "1_1") (pintype "passive"))
      (node (ref "R2") (pin "1") (pinfunction "1_1") (pintype "passive"))
      (node (ref "U3") (pin "67") (pinfunction "ANT_GNSS_67") (pintype "bidirectional"))
    )
    (net (code "40") (name "Net-(U3-ANT_LORA)") (class "Default")
      (node (ref "R16") (pin "1") (pinfunction "1_1") (pintype "passive"))
      (node (ref "U3") (pin "72") (pinfunction "ANT_LORA_72") (pintype "bidirectional"))
    )
    (net (code "41") (name "Net-(U3-ANT_WIFI)") (class "Default")
      (node (ref "L2") (pin "1") (pinfunction "1_1") (pintype "passive"))
      (node (ref "U3") (pin "65") (pinfunction "ANT_WIFI_65") (pintype "bidirectional"))
    )
    (net (code "42") (name "P0.00{slash}XL1") (class "Default")
      (node (ref "C15") (pin "1") (pinfunction "1_1") (pintype "passive"))
      (node (ref "U3") (pin "29") (pinfunction "P0.00_29") (pintype "bidirectional"))
      (node (ref "Y2") (pin "2") (pinfunction "2_2") (pintype "passive"))
    )
    (net (code "43") (name "P0.01{slash}XL2") (class "Default")
      (node (ref "C61") (pin "1") (pinfunction "1_1") (pintype "passive"))
      (node (ref "U3") (pin "30") (pinfunction "P0.01_30") (pintype "bidirectional"))
      (node (ref "Y2") (pin "1") (pinfunction "1_1") (pintype "passive"))
    )
    (net (code "44") (name "P0.02") (class "Default")
      (node (ref "J9") (pin "3") (pinfunction "3_3") (pintype "passive"))
      (node (ref "U3") (pin "12") (pinfunction "P0.02_12") (pintype "bidirectional"))
    )
    (net (code "45") (name "P0.03") (class "Default")
      (node (ref "J9") (pin "4") (pinfunction "4_4") (pintype "passive"))
      (node (ref "U3") (pin "13") (pinfunction "P0.03_13") (pintype "bidirectional"))
    )
    (net (code "46") (name "P0.04{slash}AIN2") (class "Default")
      (node (ref "J7") (pin "1") (pinfunction "1_1") (pintype "bidirectional"))
      (node (ref "U3") (pin "31") (pinfunction "P0.04_31") (pintype "bidirectional"))
    )
    (net (code "47") (name "P0.05{slash}AIN3") (class "Default")
      (node (ref "J7") (pin "2") (pinfunction "2_2") (pintype "bidirectional"))
      (node (ref "U3") (pin "17") (pinfunction "P0.05_17") (pintype "bidirectional"))
    )
    (net (code "48") (name "P0.06") (class "Default")
      (node (ref "R8") (pin "2") (pinfunction "2_2") (pintype "passive"))
      (node (ref "U3") (pin "32") (pinfunction "P0.06_32") (pintype "bidirectional"))
    )
    (net (code "49") (name "P0.07") (class "Default")
      (node (ref "J9") (pin "6") (pinfunction "6_6") (pintype "passive"))
      (node (ref "U3") (pin "19") (pinfunction "P0.07_19") (pintype "bidirectional"))
    )
    (net (code "50") (name "P0.08{slash}D2") (class "Default")
      (node (ref "J4") (pin "2") (pinfunction "2_2") (pintype "bidirectional"))
      (node (ref "U3") (pin "33") (pinfunction "P0.08_33") (pintype "bidirectional"))
    )
    (net (code "51") (name "P0.11") (class "Default")
      (node (ref "R12") (pin "1") (pinfunction "1_1") (pintype "passive"))
      (node (ref "U3") (pin "25") (pinfunction "P0.11_25") (pintype "bidirectional"))
    )
    (net (code "52") (name "P0.12{slash}D2") (class "Default")
      (node (ref "J4") (pin "1") (pinfunction "1_1") (pintype "bidirectional"))
      (node (ref "U3") (pin "35") (pinfunction "P0.12_35") (pintype "bidirectional"))
    )
    (net (code "53") (name "P0.13{slash}SDA_0") (class "Default")
      (node (ref "J6") (pin "2") (pinfunction "2_2") (pintype "bidirectional"))
      (node (ref "R20") (pin "1") (pinfunction "1_1") (pintype "passive"))
      (node (ref "U3") (pin "39") (pinfunction "P0.13_39") (pintype "bidirectional"))
    )
    (net (code "54") (name "P0.14{slash}SCL_0") (class "Default")
      (node (ref "J6") (pin "1") (pinfunction "1_1") (pintype "bidirectional"))
      (node (ref "R21") (pin "1") (pinfunction "1_1") (pintype "passive"))
      (node (ref "U3") (pin "38") (pinfunction "P0.14_38") (pintype "bidirectional"))
    )
    (net (code "55") (name "P0.15") (class "Default")
      (node (ref "J12") (pin "6") (pinfunction "6_6") (pintype "passive"))
      (node (ref "U3") (pin "42") (pinfunction "P0.15_42") (pintype "bidirectional"))
    )
    (net (code "56") (name "P0.16") (class "Default")
      (node (ref "R9") (pin "1") (pinfunction "1_1") (pintype "passive"))
      (node (ref "U3") (pin "26") (pinfunction "P0.16_26") (pintype "bidirectional"))
    )
    (net (code "57") (name "P0.17") (class "Default")
      (node (ref "J12") (pin "5") (pinfunction "5_5") (pintype "passive"))
      (node (ref "U3") (pin "43") (pinfunction "P0.17_43") (pintype "bidirectional"))
    )
    (net (code "58") (name "P0.18{slash}NRESET") (class "Default")
      (node (ref "C18") (pin "1") (pinfunction "1_1") (pintype "passive"))
      (node (ref "K1") (pin "2") (pinfunction "2_2") (pintype "passive"))
      (node (ref "R4") (pin "1") (pinfunction "1_1") (pintype "passive"))
      (node (ref "U3") (pin "36") (pinfunction "P0.18_36") (pintype "bidirectional"))
    )
    (net (code "59") (name "P0.20") (class "Default")
      (node (ref "J12") (pin "4") (pinfunction "4_4") (pintype "passive"))
      (node (ref "U3") (pin "45") (pinfunction "P0.20_45") (pintype "bidirectional"))
    )
    (net (code "60") (name "P0.21") (class "Default")
      (node (ref "J12") (pin "3") (pinfunction "3_3") (pintype "passive"))
      (node (ref "U3") (pin "49") (pinfunction "P0.21_49") (pintype "bidirectional"))
    )
    (net (code "61") (name "P0.22{slash}UART_RXD") (class "Default")
      (node (ref "J10") (pin "1") (pinfunction "1_1") (pintype "bidirectional"))
      (node (ref "U3") (pin "46") (pinfunction "P0.22_46") (pintype "bidirectional"))
    )
    (net (code "62") (name "P0.23{slash}QSPI_IO3") (class "Default")
      (node (ref "U3") (pin "59") (pinfunction "P0.23_59") (pintype "bidirectional"))
      (node (ref "U4") (pin "7") (pinfunction "/HOLD/RESET(IO3)_7") (pintype "bidirectional"))
    )
    (net (code "63") (name "P0.24{slash}UART_TXD") (class "Default")
      (node (ref "J10") (pin "2") (pinfunction "2_2") (pintype "bidirectional"))
      (node (ref "U3") (pin "47") (pinfunction "P0.24_47") (pintype "bidirectional"))
    )
    (net (code "64") (name "P0.25") (class "Default")
      (node (ref "J12") (pin "2") (pinfunction "2_2") (pintype "passive"))
      (node (ref "U3") (pin "52") (pinfunction "P0.25_52") (pintype "bidirectional"))
    )
    (net (code "65") (name "P0.26{slash}D1") (class "Default")
      (node (ref "J2") (pin "1") (pinfunction "1_1") (pintype "bidirectional"))
      (node (ref "U3") (pin "18") (pinfunction "P0.26_18") (pintype "bidirectional"))
    )
    (net (code "66") (name "P0.27{slash}D1") (class "Default")
      (node (ref "J2") (pin "2") (pinfunction "2_2") (pintype "bidirectional"))
      (node (ref "U3") (pin "16") (pinfunction "P0.27_16") (pintype "bidirectional"))
    )
    (net (code "67") (name "P0.28{slash}AIN4") (class "Default")
      (node (ref "J1") (pin "1") (pinfunction "1_1") (pintype "bidirectional"))
      (node (ref "U3") (pin "14") (pinfunction "P0.28_14") (pintype "bidirectional"))
    )
    (net (code "68") (name "P0.29{slash}AIN5") (class "Default")
      (node (ref "J1") (pin "2") (pinfunction "2_2") (pintype "bidirectional"))
      (node (ref "U3") (pin "9") (pinfunction "P0.29_9") (pintype "bidirectional"))
    )
    (net (code "69") (name "P0.30") (class "Default")
      (node (ref "J9") (pin "5") (pinfunction "5_5") (pintype "passive"))
      (node (ref "U3") (pin "15") (pinfunction "P0.30_15") (pintype "bidirectional"))
    )
    (net (code "70") (name "P1.00{slash}USER_KEY") (class "Default")
      (node (ref "C19") (pin "1") (pinfunction "1_1") (pintype "passive"))
      (node (ref "K2") (pin "2") (pinfunction "2_2") (pintype "passive"))
      (node (ref "R6") (pin "1") (pinfunction "1_1") (pintype "passive"))
      (node (ref "U3") (pin "48") (pinfunction "P1.00_48") (pintype "bidirectional"))
    )
    (net (code "71") (name "P1.01{slash}QSPI_IO2") (class "Default")
      (node (ref "U3") (pin "60") (pinfunction "P1.01_60") (pintype "bidirectional"))
      (node (ref "U4") (pin "3") (pinfunction "/WP(IO2)_3") (pintype "bidirectional"))
    )
    (net (code "72") (name "P1.02{slash}QSPI_IO0") (class "Default")
      (node (ref "U3") (pin "58") (pinfunction "P1.02_58") (pintype "bidirectional"))
      (node (ref "U4") (pin "5") (pinfunction "DI(IO0)_5") (pintype "bidirectional"))
    )
    (net (code "73") (name "P1.03{slash}QSPI_IO1") (class "Default")
      (node (ref "U3") (pin "61") (pinfunction "P1.03_61") (pintype "bidirectional"))
      (node (ref "U4") (pin "2") (pinfunction "DO(IO1)_2") (pintype "bidirectional"))
    )
    (net (code "74") (name "P1.04{slash}QSPI_SCK") (class "Default")
      (node (ref "U3") (pin "57") (pinfunction "P1.04_57") (pintype "bidirectional"))
      (node (ref "U4") (pin "6") (pinfunction "CLK_6") (pintype "bidirectional"))
    )
    (net (code "75") (name "P1.05{slash}QSPI_CS") (class "Default")
      (node (ref "U3") (pin "62") (pinfunction "P1.05_62") (pintype "bidirectional"))
      (node (ref "U4") (pin "1") (pinfunction "/CS_1") (pintype "bidirectional"))
    )
    (net (code "76") (name "P1.08") (class "Default")
      (node (ref "R11") (pin "1") (pinfunction "1_1") (pintype "passive"))
      (node (ref "U3") (pin "20") (pinfunction "P1.08_20") (pintype "bidirectional"))
    )
    (net (code "77") (name "P1.09{slash}LED") (class "Default")
      (node (ref "LED2") (pin "-") (pinfunction "-_-") (pintype "passive"))
      (node (ref "U3") (pin "34") (pinfunction "P1.09_34") (pintype "bidirectional"))
    )
    (net (code "78") (name "SWDCLK") (class "Default")
      (node (ref "J8") (pin "P$4") (pinfunction "P$4_P$4") (pintype "bidirectional"))
      (node (ref "U3") (pin "51") (pinfunction "SWDCLK_51") (pintype "bidirectional"))
    )
    (net (code "79") (name "SWDIO") (class "Default")
      (node (ref "J8") (pin "P$3") (pinfunction "P$3_P$3") (pintype "bidirectional"))
      (node (ref "U3") (pin "50") (pinfunction "SWDIO_50") (pintype "bidirectional"))
    )
    (net (code "80") (name "VDD_NRF") (class "Default")
      (node (ref "C1") (pin "1") (pinfunction "1_1") (pintype "passive"))
      (node (ref "C10") (pin "1") (pinfunction "1_1") (pintype "passive"))
      (node (ref "C2") (pin "1") (pinfunction "1_1") (pintype "passive"))
      (node (ref "FB1") (pin "1") (pinfunction "1_1") (pintype "passive"))
      (node (ref "U3") (pin "27") (pinfunction "VDD_NRF_27_27") (pintype "bidirectional"))
      (node (ref "U3") (pin "28") (pinfunction "VDD_NRF_28_28") (pintype "bidirectional"))
    )
    (net (code "81") (name "VDD_RADIO") (class "Default")
      (node (ref "C12") (pin "1") (pinfunction "1_1") (pintype "passive"))
      (node (ref "C3") (pin "1") (pinfunction "1_1") (pintype "passive"))
      (node (ref "C4") (pin "1") (pinfunction "1_1") (pintype "passive"))
      (node (ref "FB2") (pin "1") (pinfunction "1_1") (pintype "passive"))
      (node (ref "U3") (pin "21") (pinfunction "VDD_LR_21_21") (pintype "bidirectional"))
      (node (ref "U3") (pin "22") (pinfunction "VDD_LR_22_22") (pintype "bidirectional"))
    )
    (net (code "82") (name "unconnected-(ANT1-PadP$2)") (class "Default")
      (node (ref "ANT1") (pin "P$2") (pinfunction "P$2_P$2") (pintype "bidirectional"))
    )
    (net (code "83") (name "unconnected-(J3-SBU1-PadA8)") (class "Default")
      (node (ref "J3") (pin "A8") (pinfunction "SBU1_A8") (pintype "bidirectional"))
    )
    (net (code "84") (name "unconnected-(J3-SBU2-PadB8)") (class "Default")
      (node (ref "J3") (pin "B8") (pinfunction "SBU2_B8") (pintype "bidirectional"))
    )
    (net (code "85") (name "unconnected-(U3-P0.09-Pad56)") (class "Default")
      (node (ref "U3") (pin "56") (pinfunction "P0.09_56") (pintype "bidirectional"))
    )
    (net (code "86") (name "unconnected-(U3-P0.10-Pad55)") (class "Default")
      (node (ref "U3") (pin "55") (pinfunction "P0.10_55") (pintype "bidirectional"))
    )
    (net (code "87") (name "unconnected-(U3-P0.19-Pad63)") (class "Default")
      (node (ref "U3") (pin "63") (pinfunction "P0.19_63") (pintype "bidirectional"))
    )
  )
)
